# DotBar.net
KiCad netlist of a schematic drawn in EAGLE
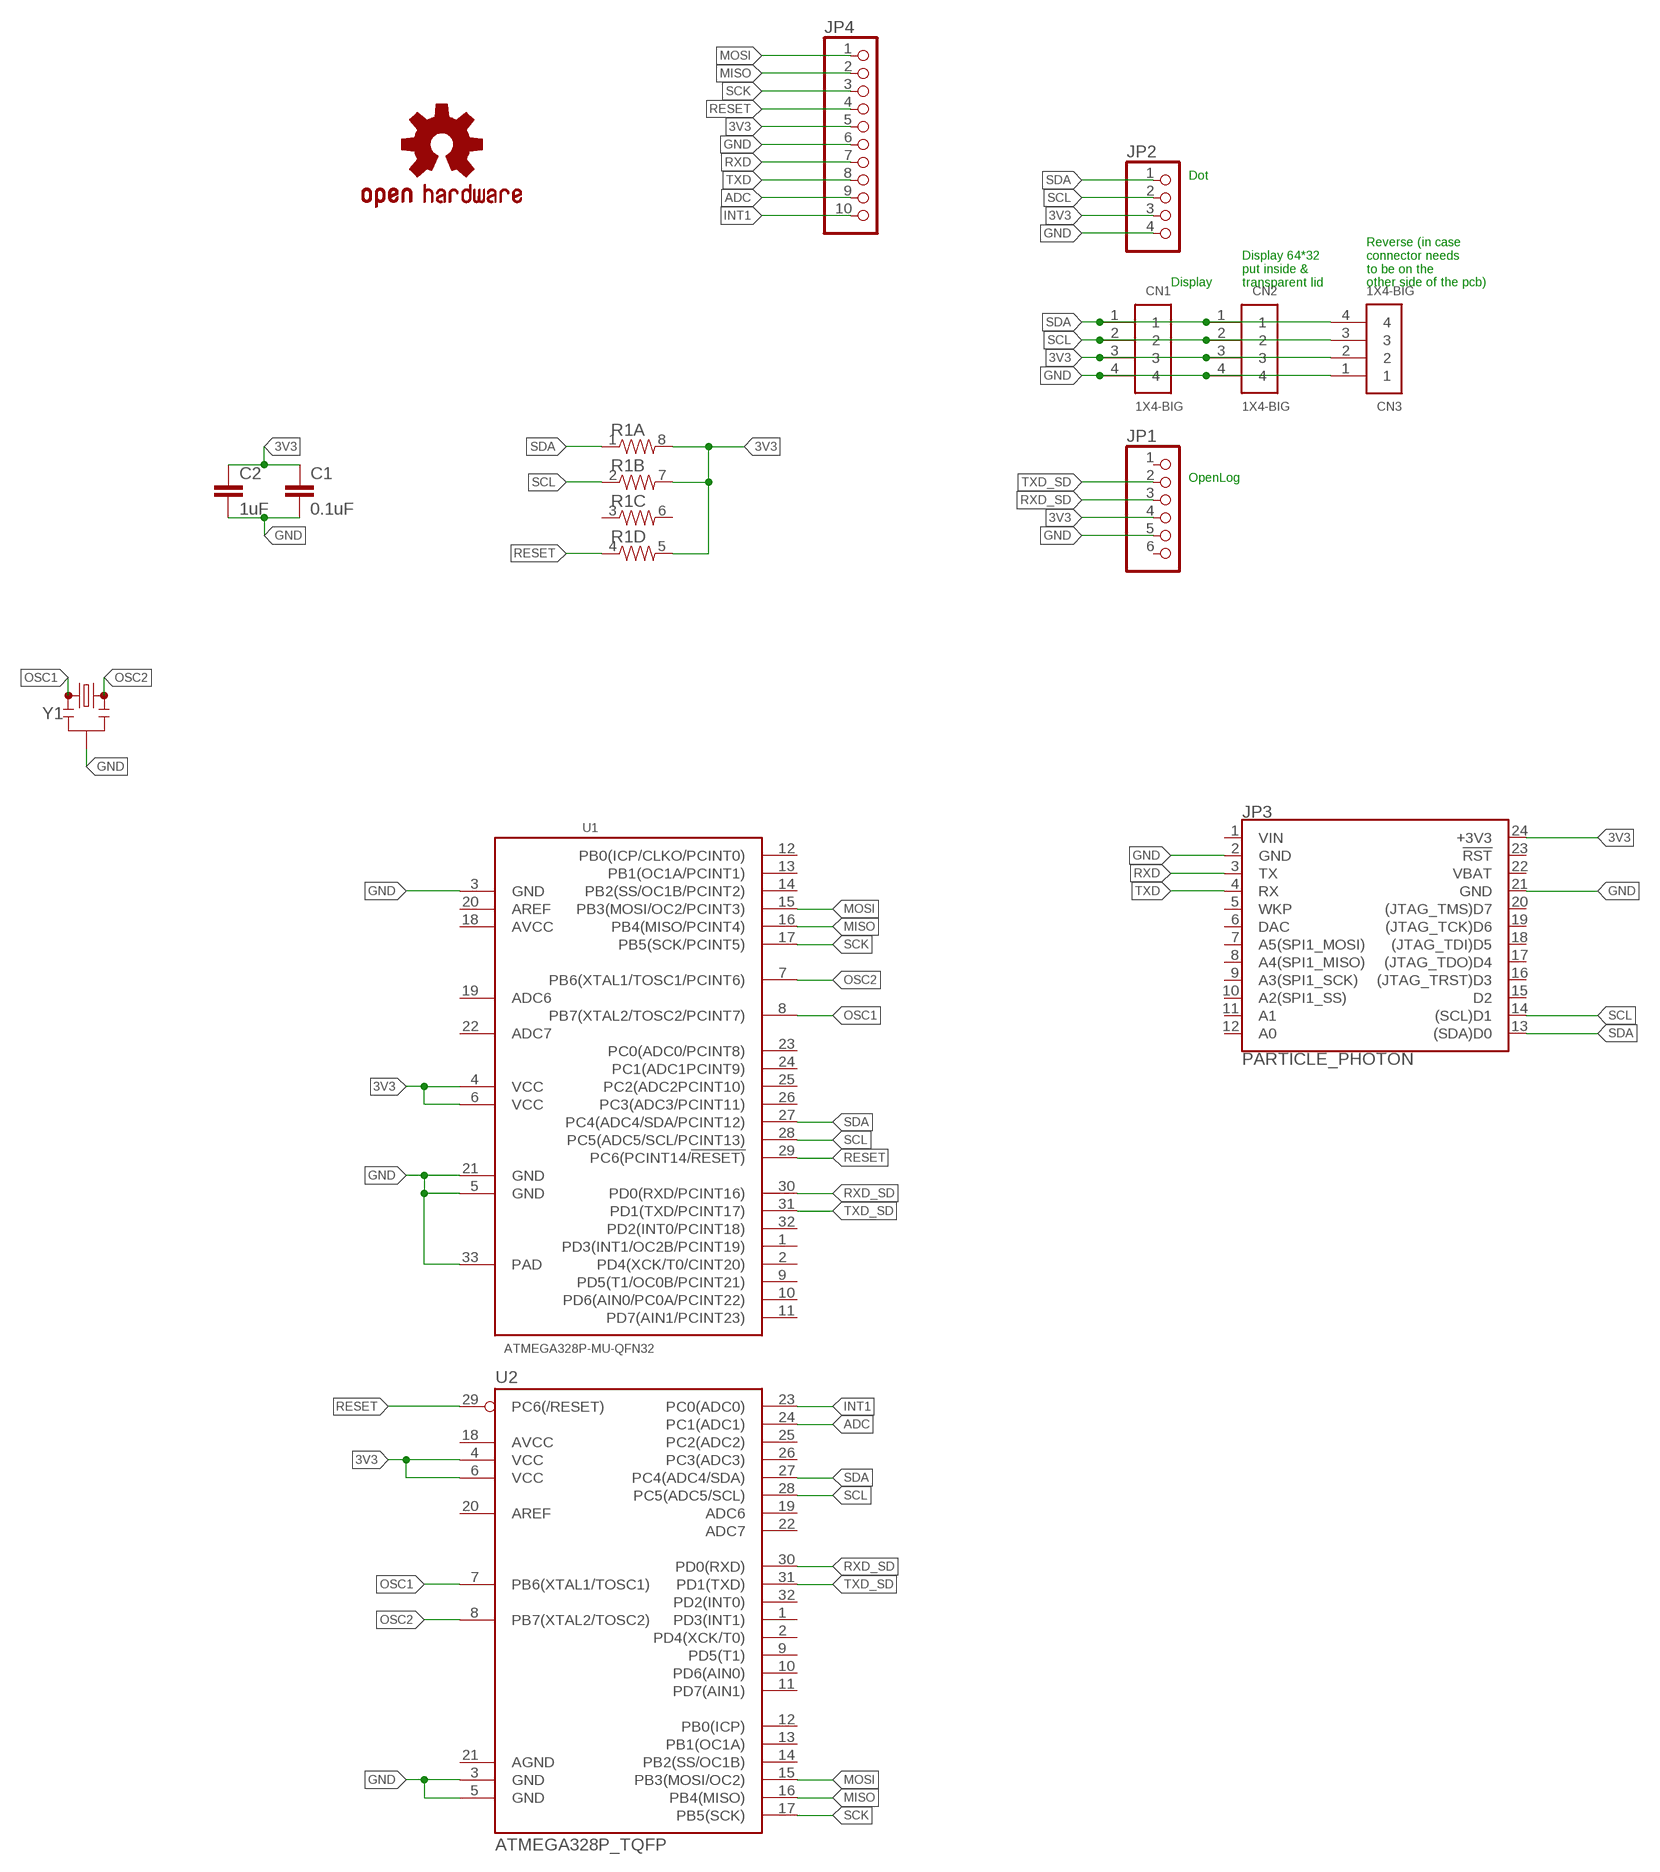
[diagram p0: schematic, sheet 1]

(export (version "E")
  (design (tool "Eeschema 10.0.6"))
  (components
    (comp (ref "C1")
      (value "0.1uF")
      (footprint "eagle-import:C0603")
      (libsource (lib "eagle-import") (part "C-EUC0603"))
    )
    (comp (ref "C2")
      (value "1uF")
      (footprint "eagle-import:C0603")
      (libsource (lib "eagle-import") (part "C-EUC0603"))
    )
    (comp (ref "CN1")
      (value "1X4-BIG")
      (footprint "eagle-import:1X04-BIG")
      (libsource (lib "eagle-import") (part "1X4-BIG"))
    )
    (comp (ref "CN2")
      (value "1X4-BIG")
      (footprint "eagle-import:1X04-BIG")
      (libsource (lib "eagle-import") (part "1X4-BIG"))
    )
    (comp (ref "CN3")
      (value "1X4-BIG")
      (footprint "eagle-import:1X04-BIG")
      (libsource (lib "eagle-import") (part "1X4-BIG"))
    )
    (comp (ref "JP1")
      (value "PINHD-1X6")
      (footprint "eagle-import:1X06")
      (libsource (lib "eagle-import") (part "PINHD-1X6"))
    )
    (comp (ref "JP2")
      (value "PINHD-1X4")
      (footprint "eagle-import:1X04")
      (libsource (lib "eagle-import") (part "PINHD-1X4"))
    )
    (comp (ref "JP3")
      (value "PARTICLE_PHOTON")
      (footprint "eagle-import:PARTICLE_PHOTON")
      (libsource (lib "eagle-import") (part "PARTICLE_PHOTON"))
    )
    (comp (ref "JP4")
      (value "PINHD-1X10")
      (footprint "eagle-import:1X10")
      (libsource (lib "eagle-import") (part "PINHD-1X10"))
    )
    (comp (ref "LOGO1")
      (value "OSHW-LOGOS")
      (footprint "eagle-import:OSHW-LOGO-S")
      (libsource (lib "eagle-import") (part "OSHW-LOGOS"))
    )
    (comp (ref "R1")
      (value "RESISTOR-ARRAY0603-ARV")
      (footprint "eagle-import:0603-ARV")
      (libsource (lib "eagle-import") (part "RESISTOR-ARRAY0603-ARV"))
    )
    (comp (ref "U1")
      (value "ATMEGA328P-MU-QFN32")
      (footprint "eagle-import:QFN32G-0.5-5X5MM")
      (fields (field (name "MPN") "ATMEGA328P-MU"))
      (libsource (lib "eagle-import") (part "MCU-ATMEGA328P-MU(QFN32)"))
    )
    (comp (ref "U2")
      (value "ATMEGA328P_TQFP")
      (footprint "eagle-import:TQFP32-08")
      (libsource (lib "eagle-import") (part "ATMEGA328P_TQFP"))
    )
    (comp (ref "Y1")
      (value "RESONATORSMD-3.2X1.3")
      (footprint "eagle-import:RESONATOR-SMD-3.2X1.3")
      (libsource (lib "eagle-import") (part "RESONATORSMD-3.2X1.3"))
    )
  )
  (nets
    (net (code "1") (name "/VBAT") (class "Default")
      (node (ref "JP3") (pin "22") (pinfunction "VBAT_22") (pintype "power_in"))
    )
    (net (code "2") (name "/VIN") (class "Default")
      (node (ref "JP3") (pin "1") (pinfunction "VIN_1") (pintype "power_in"))
    )
    (net (code "3") (name "3V3") (class "Default")
      (node (ref "C1") (pin "1") (pinfunction "1_1") (pintype "passive"))
      (node (ref "C2") (pin "1") (pinfunction "1_1") (pintype "passive"))
      (node (ref "CN1") (pin "3") (pinfunction "3_3") (pintype "bidirectional"))
      (node (ref "CN2") (pin "3") (pinfunction "3_3") (pintype "bidirectional"))
      (node (ref "CN3") (pin "2") (pinfunction "2_2") (pintype "bidirectional"))
      (node (ref "JP1") (pin "4") (pinfunction "4_4") (pintype "passive"))
      (node (ref "JP2") (pin "3") (pinfunction "3_3") (pintype "passive"))
      (node (ref "JP3") (pin "24") (pinfunction "+3V3_24") (pintype "power_in"))
      (node (ref "JP4") (pin "5") (pinfunction "5_5") (pintype "passive"))
      (node (ref "R1") (pin "5") (pinfunction "2_5") (pintype "passive"))
      (node (ref "R1") (pin "7") (pinfunction "2_7") (pintype "passive"))
      (node (ref "R1") (pin "8") (pinfunction "2_8") (pintype "passive"))
      (node (ref "U1") (pin "4") (pinfunction "VCC_4") (pintype "bidirectional"))
      (node (ref "U1") (pin "6") (pinfunction "VCC_6") (pintype "bidirectional"))
      (node (ref "U2") (pin "4") (pinfunction "VCC_4") (pintype "bidirectional"))
      (node (ref "U2") (pin "6") (pinfunction "VCC_6") (pintype "bidirectional"))
    )
    (net (code "4") (name "ADC") (class "Default")
      (node (ref "JP4") (pin "9") (pinfunction "9_9") (pintype "passive"))
      (node (ref "U2") (pin "24") (pinfunction "PC1(ADC1)_24") (pintype "bidirectional"))
    )
    (net (code "5") (name "GND") (class "Default")
      (node (ref "C1") (pin "2") (pinfunction "2_2") (pintype "passive"))
      (node (ref "C2") (pin "2") (pinfunction "2_2") (pintype "passive"))
      (node (ref "CN1") (pin "4") (pinfunction "4_4") (pintype "bidirectional"))
      (node (ref "CN2") (pin "4") (pinfunction "4_4") (pintype "bidirectional"))
      (node (ref "CN3") (pin "1") (pinfunction "1_1") (pintype "bidirectional"))
      (node (ref "JP1") (pin "5") (pinfunction "5_5") (pintype "passive"))
      (node (ref "JP2") (pin "4") (pinfunction "4_4") (pintype "passive"))
      (node (ref "JP3") (pin "2") (pinfunction "GND_2") (pintype "power_in"))
      (node (ref "JP3") (pin "21") (pinfunction "GND_21") (pintype "power_in"))
      (node (ref "JP4") (pin "6") (pinfunction "6_6") (pintype "passive"))
      (node (ref "U1") (pin "21") (pinfunction "GND_21") (pintype "bidirectional"))
      (node (ref "U1") (pin "3") (pinfunction "GND_3") (pintype "bidirectional"))
      (node (ref "U1") (pin "33") (pinfunction "PAD_33") (pintype "bidirectional"))
      (node (ref "U1") (pin "5") (pinfunction "GND_5") (pintype "bidirectional"))
      (node (ref "U2") (pin "3") (pinfunction "GND_3") (pintype "bidirectional"))
      (node (ref "U2") (pin "5") (pinfunction "GND_5") (pintype "bidirectional"))
      (node (ref "Y1") (pin "2") (pinfunction "2_2") (pintype "passive"))
    )
    (net (code "6") (name "INT1") (class "Default")
      (node (ref "JP4") (pin "10") (pinfunction "10_10") (pintype "passive"))
      (node (ref "U2") (pin "23") (pinfunction "PC0(ADC0)_23") (pintype "bidirectional"))
    )
    (net (code "7") (name "MISO") (class "Default")
      (node (ref "JP4") (pin "2") (pinfunction "2_2") (pintype "passive"))
      (node (ref "U1") (pin "16") (pinfunction "PB4(MISO/PCINT4)_16") (pintype "bidirectional"))
      (node (ref "U2") (pin "16") (pinfunction "PB4(MISO)_16") (pintype "bidirectional"))
    )
    (net (code "8") (name "MOSI") (class "Default")
      (node (ref "JP4") (pin "1") (pinfunction "1_1") (pintype "passive"))
      (node (ref "U1") (pin "15") (pinfunction "PB3(MOSI/OC2/PCINT3)_15") (pintype "bidirectional"))
      (node (ref "U2") (pin "15") (pinfunction "PB3(MOSI/OC2)_15") (pintype "bidirectional"))
    )
    (net (code "9") (name "OSC1") (class "Default")
      (node (ref "U1") (pin "8") (pinfunction "PB7(XTAL2/TOSC2/PCINT7)_8") (pintype "bidirectional"))
      (node (ref "U2") (pin "7") (pinfunction "PB6(XTAL1/TOSC1)_7") (pintype "bidirectional"))
      (node (ref "Y1") (pin "1") (pinfunction "1_1") (pintype "passive"))
    )
    (net (code "10") (name "OSC2") (class "Default")
      (node (ref "U1") (pin "7") (pinfunction "PB6(XTAL1/TOSC1/PCINT6)_7") (pintype "bidirectional"))
      (node (ref "U2") (pin "8") (pinfunction "PB7(XTAL2/TOSC2)_8") (pintype "bidirectional"))
      (node (ref "Y1") (pin "3") (pinfunction "3_3") (pintype "passive"))
    )
    (net (code "11") (name "RESET") (class "Default")
      (node (ref "JP4") (pin "4") (pinfunction "4_4") (pintype "passive"))
      (node (ref "R1") (pin "4") (pinfunction "1_4") (pintype "passive"))
      (node (ref "U1") (pin "29") (pinfunction "PC6(PCINT14/~{RESET})_29") (pintype "bidirectional"))
      (node (ref "U2") (pin "29") (pinfunction "PC6(/RESET)_29") (pintype "bidirectional"))
    )
    (net (code "12") (name "RXD") (class "Default")
      (node (ref "JP3") (pin "3") (pinfunction "TX_3") (pintype "bidirectional"))
      (node (ref "JP4") (pin "7") (pinfunction "7_7") (pintype "passive"))
    )
    (net (code "13") (name "RXD_SD") (class "Default")
      (node (ref "JP1") (pin "3") (pinfunction "3_3") (pintype "passive"))
      (node (ref "U1") (pin "30") (pinfunction "PD0(RXD/PCINT16)_30") (pintype "bidirectional"))
      (node (ref "U2") (pin "30") (pinfunction "PD0(RXD)_30") (pintype "bidirectional"))
    )
    (net (code "14") (name "SCK") (class "Default")
      (node (ref "JP4") (pin "3") (pinfunction "3_3") (pintype "passive"))
      (node (ref "U1") (pin "17") (pinfunction "PB5(SCK/PCINT5)_17") (pintype "bidirectional"))
      (node (ref "U2") (pin "17") (pinfunction "PB5(SCK)_17") (pintype "bidirectional"))
    )
    (net (code "15") (name "SCL") (class "Default")
      (node (ref "CN1") (pin "2") (pinfunction "2_2") (pintype "bidirectional"))
      (node (ref "CN2") (pin "2") (pinfunction "2_2") (pintype "bidirectional"))
      (node (ref "CN3") (pin "3") (pinfunction "3_3") (pintype "bidirectional"))
      (node (ref "JP2") (pin "2") (pinfunction "2_2") (pintype "passive"))
      (node (ref "JP3") (pin "14") (pinfunction "(SCL)D1_14") (pintype "bidirectional"))
      (node (ref "R1") (pin "2") (pinfunction "1_2") (pintype "passive"))
      (node (ref "U1") (pin "28") (pinfunction "PC5(ADC5/SCL/PCINT13)_28") (pintype "bidirectional"))
      (node (ref "U2") (pin "28") (pinfunction "PC5(ADC5/SCL)_28") (pintype "bidirectional"))
    )
    (net (code "16") (name "SDA") (class "Default")
      (node (ref "CN1") (pin "1") (pinfunction "1_1") (pintype "bidirectional"))
      (node (ref "CN2") (pin "1") (pinfunction "1_1") (pintype "bidirectional"))
      (node (ref "CN3") (pin "4") (pinfunction "4_4") (pintype "bidirectional"))
      (node (ref "JP2") (pin "1") (pinfunction "1_1") (pintype "passive"))
      (node (ref "JP3") (pin "13") (pinfunction "(SDA)D0_13") (pintype "bidirectional"))
      (node (ref "R1") (pin "1") (pinfunction "1_1") (pintype "passive"))
      (node (ref "U1") (pin "27") (pinfunction "PC4(ADC4/SDA/PCINT12)_27") (pintype "bidirectional"))
      (node (ref "U2") (pin "27") (pinfunction "PC4(ADC4/SDA)_27") (pintype "bidirectional"))
    )
    (net (code "17") (name "TXD") (class "Default")
      (node (ref "JP3") (pin "4") (pinfunction "RX_4") (pintype "bidirectional"))
      (node (ref "JP4") (pin "8") (pinfunction "8_8") (pintype "passive"))
    )
    (net (code "18") (name "TXD_SD") (class "Default")
      (node (ref "JP1") (pin "2") (pinfunction "2_2") (pintype "passive"))
      (node (ref "U1") (pin "31") (pinfunction "PD1(TXD/PCINT17)_31") (pintype "bidirectional"))
      (node (ref "U2") (pin "31") (pinfunction "PD1(TXD)_31") (pintype "bidirectional"))
    )
    (net (code "19") (name "unconnected-(JP1-Pad1)") (class "Default")
      (node (ref "JP1") (pin "1") (pinfunction "1_1") (pintype "passive"))
    )
    (net (code "20") (name "unconnected-(JP1-Pad6)") (class "Default")
      (node (ref "JP1") (pin "6") (pinfunction "6_6") (pintype "passive"))
    )
    (net (code "21") (name "unconnected-(JP3-(JTAG_TCK)D6-Pad19)") (class "Default")
      (node (ref "JP3") (pin "19") (pinfunction "(JTAG_TCK)D6_19") (pintype "bidirectional"))
    )
    (net (code "22") (name "unconnected-(JP3-(JTAG_TDI)D5-Pad18)") (class "Default")
      (node (ref "JP3") (pin "18") (pinfunction "(JTAG_TDI)D5_18") (pintype "bidirectional"))
    )
    (net (code "23") (name "unconnected-(JP3-(JTAG_TDO)D4-Pad17)") (class "Default")
      (node (ref "JP3") (pin "17") (pinfunction "(JTAG_TDO)D4_17") (pintype "bidirectional"))
    )
    (net (code "24") (name "unconnected-(JP3-(JTAG_TMS)D7-Pad20)") (class "Default")
      (node (ref "JP3") (pin "20") (pinfunction "(JTAG_TMS)D7_20") (pintype "bidirectional"))
    )
    (net (code "25") (name "unconnected-(JP3-(JTAG_TRST)D3-Pad16)") (class "Default")
      (node (ref "JP3") (pin "16") (pinfunction "(JTAG_TRST)D3_16") (pintype "bidirectional"))
    )
    (net (code "26") (name "unconnected-(JP3-A0-Pad12)") (class "Default")
      (node (ref "JP3") (pin "12") (pinfunction "A0_12") (pintype "bidirectional"))
    )
    (net (code "27") (name "unconnected-(JP3-A1-Pad11)") (class "Default")
      (node (ref "JP3") (pin "11") (pinfunction "A1_11") (pintype "bidirectional"))
    )
    (net (code "28") (name "unconnected-(JP3-A2(SPI1_SS)-Pad10)") (class "Default")
      (node (ref "JP3") (pin "10") (pinfunction "A2(SPI1_SS)_10") (pintype "bidirectional"))
    )
    (net (code "29") (name "unconnected-(JP3-A3(SPI1_SCK)-Pad9)") (class "Default")
      (node (ref "JP3") (pin "9") (pinfunction "A3(SPI1_SCK)_9") (pintype "bidirectional"))
    )
    (net (code "30") (name "unconnected-(JP3-A4(SPI1_MISO)-Pad8)") (class "Default")
      (node (ref "JP3") (pin "8") (pinfunction "A4(SPI1_MISO)_8") (pintype "bidirectional"))
    )
    (net (code "31") (name "unconnected-(JP3-A5(SPI1_MOSI)-Pad7)") (class "Default")
      (node (ref "JP3") (pin "7") (pinfunction "A5(SPI1_MOSI)_7") (pintype "bidirectional"))
    )
    (net (code "32") (name "unconnected-(JP3-D2-Pad15)") (class "Default")
      (node (ref "JP3") (pin "15") (pinfunction "D2_15") (pintype "bidirectional"))
    )
    (net (code "33") (name "unconnected-(JP3-DAC-Pad6)") (class "Default")
      (node (ref "JP3") (pin "6") (pinfunction "DAC_6") (pintype "bidirectional"))
    )
    (net (code "34") (name "unconnected-(JP3-WKP-Pad5)") (class "Default")
      (node (ref "JP3") (pin "5") (pinfunction "WKP_5") (pintype "bidirectional"))
    )
    (net (code "35") (name "unconnected-(JP3-~{RST}-Pad23)") (class "Default")
      (node (ref "JP3") (pin "23") (pinfunction "~{RST}_23") (pintype "bidirectional"))
    )
    (net (code "36") (name "unconnected-(R1C-1-Pad3)") (class "Default")
      (node (ref "R1") (pin "3") (pinfunction "1_3") (pintype "passive"))
    )
    (net (code "37") (name "unconnected-(R1C-2-Pad6)") (class "Default")
      (node (ref "R1") (pin "6") (pinfunction "2_6") (pintype "passive"))
    )
    (net (code "38") (name "unconnected-(U1-ADC6-Pad19)") (class "Default")
      (node (ref "U1") (pin "19") (pinfunction "ADC6_19") (pintype "bidirectional"))
    )
    (net (code "39") (name "unconnected-(U1-ADC7-Pad22)") (class "Default")
      (node (ref "U1") (pin "22") (pinfunction "ADC7_22") (pintype "bidirectional"))
    )
    (net (code "40") (name "unconnected-(U1-AREF-Pad20)") (class "Default")
      (node (ref "U1") (pin "20") (pinfunction "AREF_20") (pintype "bidirectional"))
    )
    (net (code "41") (name "unconnected-(U1-AVCC-Pad18)") (class "Default")
      (node (ref "U1") (pin "18") (pinfunction "AVCC_18") (pintype "bidirectional"))
    )
    (net (code "42") (name "unconnected-(U1-PB0(ICP{slash}CLKO{slash}PCINT0)-Pad12)") (class "Default")
      (node (ref "U1") (pin "12") (pinfunction "PB0(ICP/CLKO/PCINT0)_12") (pintype "bidirectional"))
    )
    (net (code "43") (name "unconnected-(U1-PB1(OC1A{slash}PCINT1)-Pad13)") (class "Default")
      (node (ref "U1") (pin "13") (pinfunction "PB1(OC1A/PCINT1)_13") (pintype "bidirectional"))
    )
    (net (code "44") (name "unconnected-(U1-PB2(SS{slash}OC1B{slash}PCINT2)-Pad14)") (class "Default")
      (node (ref "U1") (pin "14") (pinfunction "PB2(SS/OC1B/PCINT2)_14") (pintype "bidirectional"))
    )
    (net (code "45") (name "unconnected-(U1-PC0(ADC0{slash}PCINT8)-Pad23)") (class "Default")
      (node (ref "U1") (pin "23") (pinfunction "PC0(ADC0/PCINT8)_23") (pintype "bidirectional"))
    )
    (net (code "46") (name "unconnected-(U1-PC1(ADC1PCINT9)-Pad24)") (class "Default")
      (node (ref "U1") (pin "24") (pinfunction "PC1(ADC1PCINT9)_24") (pintype "bidirectional"))
    )
    (net (code "47") (name "unconnected-(U1-PC2(ADC2PCINT10)-Pad25)") (class "Default")
      (node (ref "U1") (pin "25") (pinfunction "PC2(ADC2PCINT10)_25") (pintype "bidirectional"))
    )
    (net (code "48") (name "unconnected-(U1-PC3(ADC3{slash}PCINT11)-Pad26)") (class "Default")
      (node (ref "U1") (pin "26") (pinfunction "PC3(ADC3/PCINT11)_26") (pintype "bidirectional"))
    )
    (net (code "49") (name "unconnected-(U1-PD2(INT0{slash}PCINT18)-Pad32)") (class "Default")
      (node (ref "U1") (pin "32") (pinfunction "PD2(INT0/PCINT18)_32") (pintype "bidirectional"))
    )
    (net (code "50") (name "unconnected-(U1-PD3(INT1{slash}OC2B{slash}PCINT19)-Pad1)") (class "Default")
      (node (ref "U1") (pin "1") (pinfunction "PD3(INT1/OC2B/PCINT19)_1") (pintype "bidirectional"))
    )
    (net (code "51") (name "unconnected-(U1-PD4(XCK{slash}T0{slash}CINT20)-Pad2)") (class "Default")
      (node (ref "U1") (pin "2") (pinfunction "PD4(XCK/T0/CINT20)_2") (pintype "bidirectional"))
    )
    (net (code "52") (name "unconnected-(U1-PD5(T1{slash}OC0B{slash}PCINT21)-Pad9)") (class "Default")
      (node (ref "U1") (pin "9") (pinfunction "PD5(T1/OC0B/PCINT21)_9") (pintype "bidirectional"))
    )
    (net (code "53") (name "unconnected-(U1-PD6(AIN0{slash}PC0A{slash}PCINT22)-Pad10)") (class "Default")
      (node (ref "U1") (pin "10") (pinfunction "PD6(AIN0/PC0A/PCINT22)_10") (pintype "bidirectional"))
    )
    (net (code "54") (name "unconnected-(U1-PD7(AIN1{slash}PCINT23)-Pad11)") (class "Default")
      (node (ref "U1") (pin "11") (pinfunction "PD7(AIN1/PCINT23)_11") (pintype "bidirectional"))
    )
    (net (code "55") (name "unconnected-(U2-ADC6-Pad19)") (class "Default")
      (node (ref "U2") (pin "19") (pinfunction "ADC6_19") (pintype "bidirectional"))
    )
    (net (code "56") (name "unconnected-(U2-ADC7-Pad22)") (class "Default")
      (node (ref "U2") (pin "22") (pinfunction "ADC7_22") (pintype "bidirectional"))
    )
    (net (code "57") (name "unconnected-(U2-AGND-Pad21)") (class "Default")
      (node (ref "U2") (pin "21") (pinfunction "AGND_21") (pintype "bidirectional"))
    )
    (net (code "58") (name "unconnected-(U2-AREF-Pad20)") (class "Default")
      (node (ref "U2") (pin "20") (pinfunction "AREF_20") (pintype "bidirectional"))
    )
    (net (code "59") (name "unconnected-(U2-AVCC-Pad18)") (class "Default")
      (node (ref "U2") (pin "18") (pinfunction "AVCC_18") (pintype "bidirectional"))
    )
    (net (code "60") (name "unconnected-(U2-PB0(ICP)-Pad12)") (class "Default")
      (node (ref "U2") (pin "12") (pinfunction "PB0(ICP)_12") (pintype "bidirectional"))
    )
    (net (code "61") (name "unconnected-(U2-PB1(OC1A)-Pad13)") (class "Default")
      (node (ref "U2") (pin "13") (pinfunction "PB1(OC1A)_13") (pintype "bidirectional"))
    )
    (net (code "62") (name "unconnected-(U2-PB2(SS{slash}OC1B)-Pad14)") (class "Default")
      (node (ref "U2") (pin "14") (pinfunction "PB2(SS/OC1B)_14") (pintype "bidirectional"))
    )
    (net (code "63") (name "unconnected-(U2-PC2(ADC2)-Pad25)") (class "Default")
      (node (ref "U2") (pin "25") (pinfunction "PC2(ADC2)_25") (pintype "bidirectional"))
    )
    (net (code "64") (name "unconnected-(U2-PC3(ADC3)-Pad26)") (class "Default")
      (node (ref "U2") (pin "26") (pinfunction "PC3(ADC3)_26") (pintype "bidirectional"))
    )
    (net (code "65") (name "unconnected-(U2-PD2(INT0)-Pad32)") (class "Default")
      (node (ref "U2") (pin "32") (pinfunction "PD2(INT0)_32") (pintype "bidirectional"))
    )
    (net (code "66") (name "unconnected-(U2-PD3(INT1)-Pad1)") (class "Default")
      (node (ref "U2") (pin "1") (pinfunction "PD3(INT1)_1") (pintype "bidirectional"))
    )
    (net (code "67") (name "unconnected-(U2-PD4(XCK{slash}T0)-Pad2)") (class "Default")
      (node (ref "U2") (pin "2") (pinfunction "PD4(XCK/T0)_2") (pintype "bidirectional"))
    )
    (net (code "68") (name "unconnected-(U2-PD5(T1)-Pad9)") (class "Default")
      (node (ref "U2") (pin "9") (pinfunction "PD5(T1)_9") (pintype "bidirectional"))
    )
    (net (code "69") (name "unconnected-(U2-PD6(AIN0)-Pad10)") (class "Default")
      (node (ref "U2") (pin "10") (pinfunction "PD6(AIN0)_10") (pintype "bidirectional"))
    )
    (net (code "70") (name "unconnected-(U2-PD7(AIN1)-Pad11)") (class "Default")
      (node (ref "U2") (pin "11") (pinfunction "PD7(AIN1)_11") (pintype "bidirectional"))
    )
  )
)
